# BMS_board_layout_version.net
KiCad netlist of a schematic drawn in EAGLE
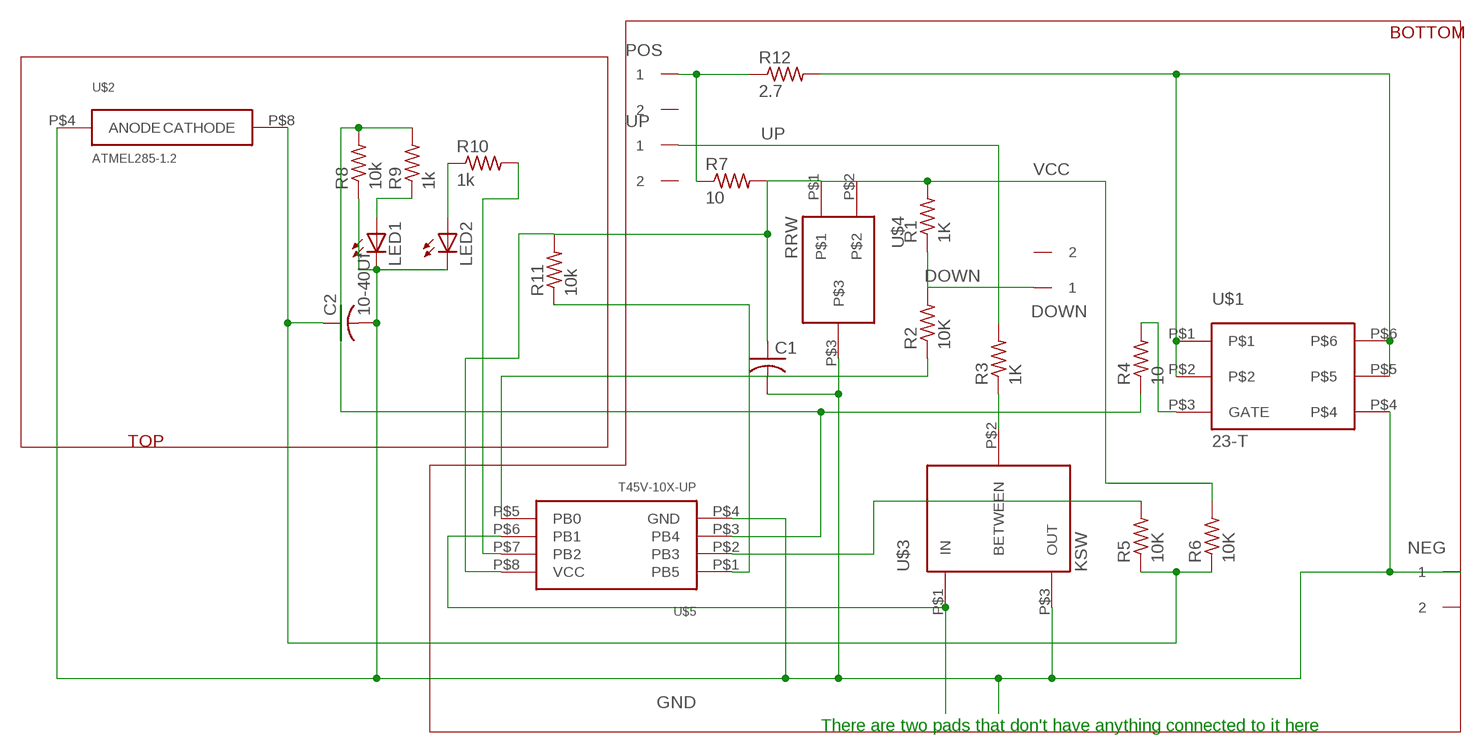
[diagram p0: schematic, sheet 1]

(export (version "E")
  (design (tool "Eeschema 10.0.6"))
  (components
    (comp (ref "C1")
      (value "C-USC0805")
      (footprint "eagle-import:C0805")
      (libsource (lib "eagle-import") (part "C-USC0805"))
    )
    (comp (ref "C2")
      (value "10-40Uf")
      (footprint "eagle-import:C0805")
      (libsource (lib "eagle-import") (part "C-USC0805"))
    )
    (comp (ref "DOWN")
      (value "CONN_1")
      (footprint "eagle-import:CONNECTOR_1")
      (libsource (lib "eagle-import") (part "CONN_1"))
    )
    (comp (ref "LED1")
      (value "LEDCHIPLED_1206")
      (footprint "eagle-import:CHIPLED_1206")
      (libsource (lib "eagle-import") (part "LEDCHIPLED_1206"))
    )
    (comp (ref "LED2")
      (value "LEDCHIPLED_1206")
      (footprint "eagle-import:CHIPLED_1206")
      (libsource (lib "eagle-import") (part "LEDCHIPLED_1206"))
    )
    (comp (ref "NEG")
      (value "CONN_1")
      (footprint "eagle-import:CONNECTOR_1")
      (libsource (lib "eagle-import") (part "CONN_1"))
    )
    (comp (ref "POS")
      (value "CONN_1")
      (footprint "eagle-import:CONNECTOR_1")
      (libsource (lib "eagle-import") (part "CONN_1"))
    )
    (comp (ref "R1")
      (value "1K")
      (footprint "eagle-import:R0805")
      (libsource (lib "eagle-import") (part "R-US_R0805"))
    )
    (comp (ref "R2")
      (value "10K")
      (footprint "eagle-import:R0805")
      (libsource (lib "eagle-import") (part "R-US_R0805"))
    )
    (comp (ref "R3")
      (value "1K")
      (footprint "eagle-import:R0805")
      (libsource (lib "eagle-import") (part "R-US_R0805"))
    )
    (comp (ref "R4")
      (value "10")
      (footprint "eagle-import:R0805")
      (libsource (lib "eagle-import") (part "R-US_R0805"))
    )
    (comp (ref "R5")
      (value "10K")
      (footprint "eagle-import:R0805")
      (libsource (lib "eagle-import") (part "R-US_R0805"))
    )
    (comp (ref "R6")
      (value "10K")
      (footprint "eagle-import:R0805")
      (libsource (lib "eagle-import") (part "R-US_R0805"))
    )
    (comp (ref "R7")
      (value "10")
      (footprint "eagle-import:R0805")
      (libsource (lib "eagle-import") (part "R-US_R0805"))
    )
    (comp (ref "R8")
      (value "10k")
      (footprint "eagle-import:R0805")
      (libsource (lib "eagle-import") (part "R-US_R0805"))
    )
    (comp (ref "R9")
      (value "1k")
      (footprint "eagle-import:R0805")
      (libsource (lib "eagle-import") (part "R-US_R0805"))
    )
    (comp (ref "R10")
      (value "1k")
      (footprint "eagle-import:R0805")
      (libsource (lib "eagle-import") (part "R-US_R0805"))
    )
    (comp (ref "R11")
      (value "10k")
      (footprint "eagle-import:R0805")
      (libsource (lib "eagle-import") (part "R-US_R0805"))
    )
    (comp (ref "R12")
      (value "2.7")
      (footprint "eagle-import:R0805")
      (libsource (lib "eagle-import") (part "R-US_R0805"))
    )
    (comp (ref "U$1")
      (value "23-T")
      (footprint "eagle-import:SOT-23-6")
      (libsource (lib "eagle-import") (part "23-T"))
    )
    (comp (ref "U$2")
      (value "ATMEL285-1.2")
      (footprint "eagle-import:8-SOIC")
      (libsource (lib "eagle-import") (part "ATMEL285-1.2"))
    )
    (comp (ref "U$3")
      (value "KSW")
      (footprint "eagle-import:SOT23-3")
      (libsource (lib "eagle-import") (part "KSW"))
    )
    (comp (ref "U$4")
      (value "RRW")
      (footprint "eagle-import:SOT23-3")
      (libsource (lib "eagle-import") (part "RRW"))
    )
    (comp (ref "U$5")
      (value "T45V-10X-UP")
      (footprint "eagle-import:TSOP-8")
      (libsource (lib "eagle-import") (part "T45V-10X-UP"))
    )
    (comp (ref "UP")
      (value "CONN_1")
      (footprint "eagle-import:CONNECTOR_1")
      (libsource (lib "eagle-import") (part "CONN_1"))
    )
  )
  (nets
    (net (code "1") (name "/DOWN") (class "Default")
      (node (ref "DOWN") (pin "1") (pinfunction "1_1") (pintype "bidirectional"))
      (node (ref "R1") (pin "1") (pinfunction "1_1") (pintype "passive"))
      (node (ref "R2") (pin "2") (pinfunction "2_2") (pintype "passive"))
    )
    (net (code "2") (name "/GND") (class "Default")
      (node (ref "C1") (pin "2") (pinfunction "2_2") (pintype "passive"))
      (node (ref "C2") (pin "2") (pinfunction "2_2") (pintype "passive"))
      (node (ref "LED1") (pin "C") (pinfunction "C_C") (pintype "passive"))
      (node (ref "LED2") (pin "C") (pinfunction "C_C") (pintype "passive"))
      (node (ref "NEG") (pin "1") (pinfunction "1_1") (pintype "bidirectional"))
      (node (ref "R8") (pin "1") (pinfunction "1_1") (pintype "passive"))
      (node (ref "U$1") (pin "P$4") (pinfunction "P$4_P$4") (pintype "bidirectional"))
      (node (ref "U$2") (pin "P$4") (pinfunction "ANODE_P$4") (pintype "bidirectional"))
      (node (ref "U$3") (pin "P$3") (pinfunction "OUT_P$3") (pintype "bidirectional"))
      (node (ref "U$4") (pin "P$3") (pinfunction "P$3_P$3") (pintype "bidirectional"))
      (node (ref "U$5") (pin "P$4") (pinfunction "GND_P$4") (pintype "bidirectional"))
    )
    (net (code "3") (name "/UP") (class "Default")
      (node (ref "R3") (pin "2") (pinfunction "2_2") (pintype "passive"))
      (node (ref "UP") (pin "1") (pinfunction "1_1") (pintype "bidirectional"))
    )
    (net (code "4") (name "/VCC") (class "Default")
      (node (ref "C1") (pin "1") (pinfunction "1_1") (pintype "passive"))
      (node (ref "R1") (pin "2") (pinfunction "2_2") (pintype "passive"))
      (node (ref "R11") (pin "2") (pinfunction "2_2") (pintype "passive"))
      (node (ref "R6") (pin "2") (pinfunction "2_2") (pintype "passive"))
      (node (ref "R7") (pin "2") (pinfunction "2_2") (pintype "passive"))
      (node (ref "U$4") (pin "P$1") (pinfunction "P$1_P$1") (pintype "bidirectional"))
      (node (ref "U$4") (pin "P$2") (pinfunction "P$2_P$2") (pintype "bidirectional"))
      (node (ref "U$5") (pin "P$8") (pinfunction "VCC_P$8") (pintype "bidirectional"))
    )
    (net (code "5") (name "Net-(LED1-PadA)") (class "Default")
      (node (ref "LED1") (pin "A") (pinfunction "A_A") (pintype "passive"))
      (node (ref "R9") (pin "1") (pinfunction "1_1") (pintype "passive"))
    )
    (net (code "6") (name "Net-(LED2-PadA)") (class "Default")
      (node (ref "LED2") (pin "A") (pinfunction "A_A") (pintype "passive"))
      (node (ref "R10") (pin "1") (pinfunction "1_1") (pintype "passive"))
    )
    (net (code "7") (name "Net-(POS-Pad1)") (class "Default")
      (node (ref "POS") (pin "1") (pinfunction "1_1") (pintype "bidirectional"))
      (node (ref "R12") (pin "1") (pinfunction "1_1") (pintype "passive"))
      (node (ref "R7") (pin "1") (pinfunction "1_1") (pintype "passive"))
    )
    (net (code "8") (name "Net-(R12-Pad2)") (class "Default")
      (node (ref "R12") (pin "2") (pinfunction "2_2") (pintype "passive"))
      (node (ref "U$1") (pin "P$1") (pinfunction "P$1_P$1") (pintype "bidirectional"))
      (node (ref "U$1") (pin "P$2") (pinfunction "P$2_P$2") (pintype "bidirectional"))
      (node (ref "U$1") (pin "P$5") (pinfunction "P$5_P$5") (pintype "bidirectional"))
      (node (ref "U$1") (pin "P$6") (pinfunction "P$6_P$6") (pintype "bidirectional"))
    )
    (net (code "9") (name "Net-(U$1-GATE)") (class "Default")
      (node (ref "R4") (pin "2") (pinfunction "2_2") (pintype "passive"))
      (node (ref "U$1") (pin "P$3") (pinfunction "GATE_P$3") (pintype "bidirectional"))
    )
    (net (code "10") (name "Net-(U$2-CATHODE)") (class "Default")
      (node (ref "C2") (pin "1") (pinfunction "1_1") (pintype "passive"))
      (node (ref "R5") (pin "1") (pinfunction "1_1") (pintype "passive"))
      (node (ref "R6") (pin "1") (pinfunction "1_1") (pintype "passive"))
      (node (ref "U$2") (pin "P$8") (pinfunction "CATHODE_P$8") (pintype "bidirectional"))
    )
    (net (code "11") (name "Net-(U$3-BETWEEN)") (class "Default")
      (node (ref "R3") (pin "1") (pinfunction "1_1") (pintype "passive"))
      (node (ref "U$3") (pin "P$2") (pinfunction "BETWEEN_P$2") (pintype "bidirectional"))
    )
    (net (code "12") (name "Net-(U$3-IN)") (class "Default")
      (node (ref "U$3") (pin "P$1") (pinfunction "IN_P$1") (pintype "bidirectional"))
      (node (ref "U$5") (pin "P$6") (pinfunction "PB1_P$6") (pintype "bidirectional"))
    )
    (net (code "13") (name "Net-(U$5-PB0)") (class "Default")
      (node (ref "R2") (pin "1") (pinfunction "1_1") (pintype "passive"))
      (node (ref "U$5") (pin "P$5") (pinfunction "PB0_P$5") (pintype "bidirectional"))
    )
    (net (code "14") (name "Net-(U$5-PB2)") (class "Default")
      (node (ref "R10") (pin "2") (pinfunction "2_2") (pintype "passive"))
      (node (ref "U$5") (pin "P$7") (pinfunction "PB2_P$7") (pintype "bidirectional"))
    )
    (net (code "15") (name "Net-(U$5-PB3)") (class "Default")
      (node (ref "R5") (pin "2") (pinfunction "2_2") (pintype "passive"))
      (node (ref "U$5") (pin "P$2") (pinfunction "PB3_P$2") (pintype "bidirectional"))
    )
    (net (code "16") (name "Net-(U$5-PB4)") (class "Default")
      (node (ref "R4") (pin "1") (pinfunction "1_1") (pintype "passive"))
      (node (ref "R8") (pin "2") (pinfunction "2_2") (pintype "passive"))
      (node (ref "R9") (pin "2") (pinfunction "2_2") (pintype "passive"))
      (node (ref "U$5") (pin "P$3") (pinfunction "PB4_P$3") (pintype "bidirectional"))
    )
    (net (code "17") (name "Net-(U$5-PB5)") (class "Default")
      (node (ref "R11") (pin "1") (pinfunction "1_1") (pintype "passive"))
      (node (ref "U$5") (pin "P$1") (pinfunction "PB5_P$1") (pintype "bidirectional"))
    )
    (net (code "18") (name "unconnected-(DOWN-Pad2)") (class "Default")
      (node (ref "DOWN") (pin "2") (pinfunction "2_2") (pintype "bidirectional"))
    )
    (net (code "19") (name "unconnected-(NEG-Pad2)") (class "Default")
      (node (ref "NEG") (pin "2") (pinfunction "2_2") (pintype "bidirectional"))
    )
    (net (code "20") (name "unconnected-(POS-Pad2)") (class "Default")
      (node (ref "POS") (pin "2") (pinfunction "2_2") (pintype "bidirectional"))
    )
    (net (code "21") (name "unconnected-(UP-Pad2)") (class "Default")
      (node (ref "UP") (pin "2") (pinfunction "2_2") (pintype "bidirectional"))
    )
  )
)
